# 8x8matrix_tlc4.net
KiCad netlist of a schematic drawn in EAGLE
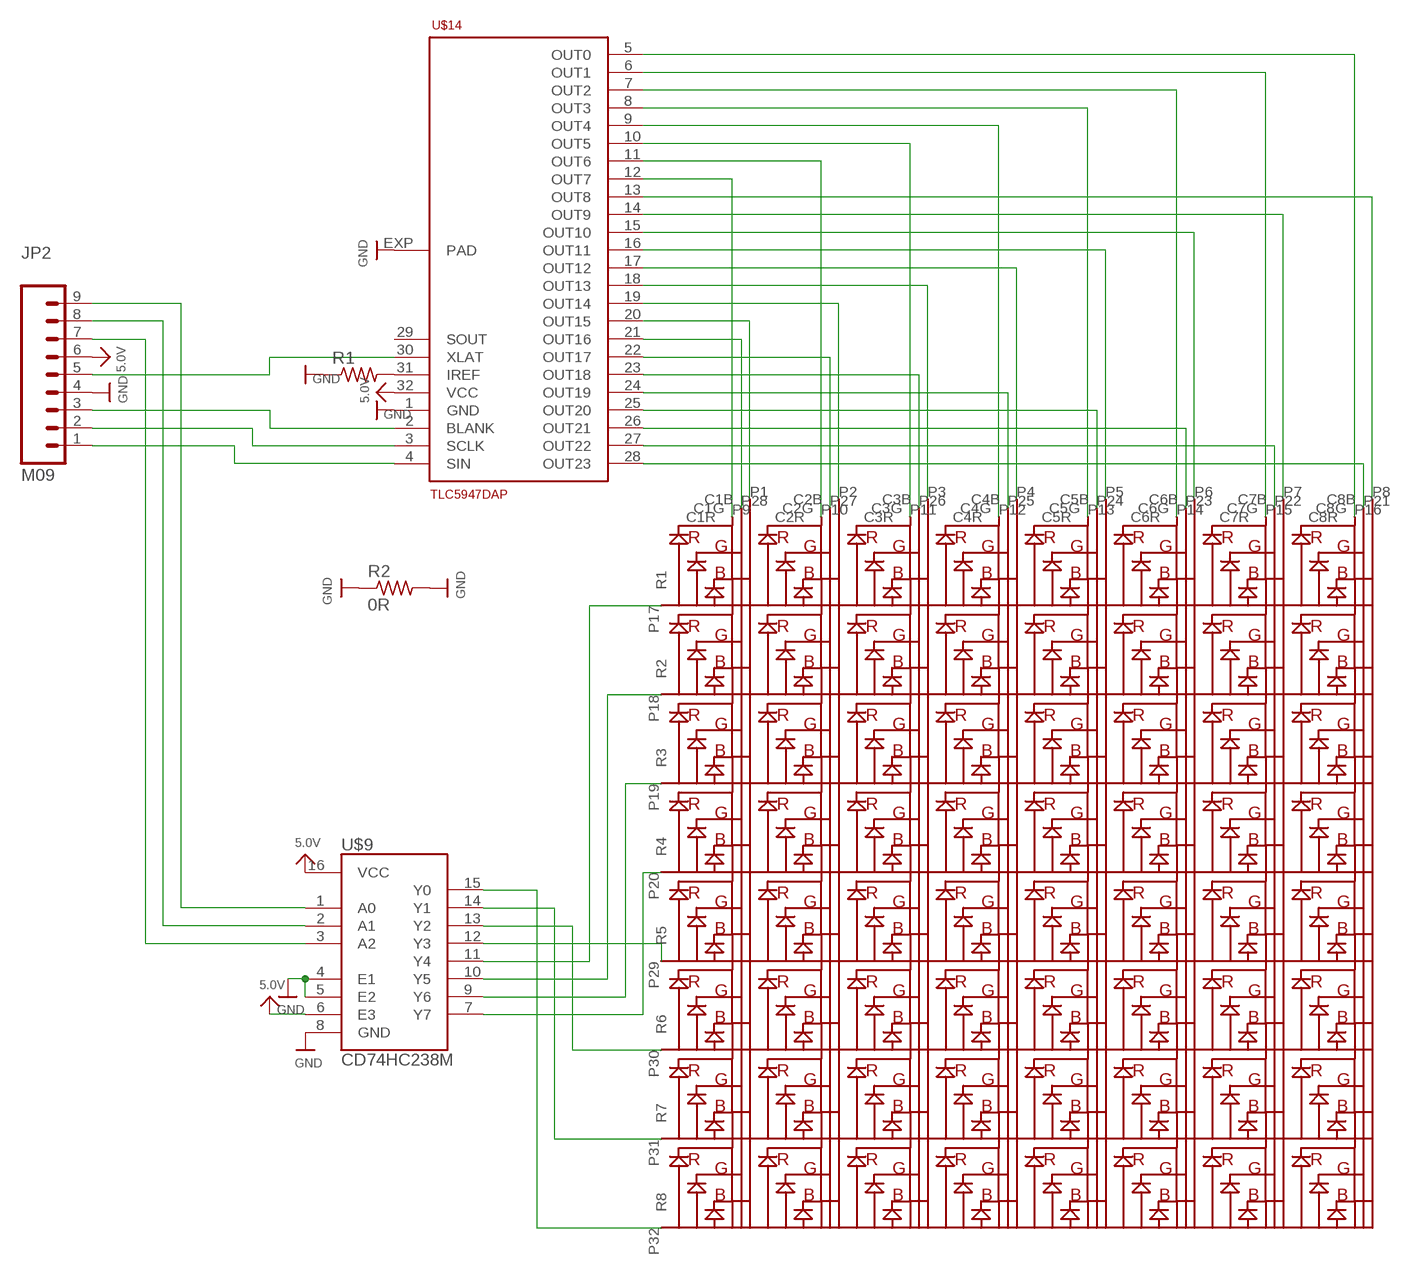
[diagram p0: schematic, sheet 1]

(export (version "E")
  (design (tool "Eeschema 10.0.6"))
  (components
    (comp (ref "JP2")
      (value "M09")
      (footprint "eagle-import:1X09")
      (libsource (lib "eagle-import") (part "M09"))
    )
    (comp (ref "R1")
      (value "R-US_R0805")
      (footprint "eagle-import:R0805")
      (libsource (lib "eagle-import") (part "R-US_R0805"))
    )
    (comp (ref "R2")
      (value "0R")
      (footprint "eagle-import:M1206")
      (libsource (lib "eagle-import") (part "R-US_M1206"))
    )
    (comp (ref "U$1")
      (value "GTM2088ARGB")
      (footprint "eagle-import:8X8MATRIX")
      (libsource (lib "eagle-import") (part "GTM2088ARGB"))
    )
    (comp (ref "U$9")
      (value "CD74HC238M")
      (footprint "eagle-import:SO-16")
      (libsource (lib "eagle-import") (part "CD74HC238M"))
    )
    (comp (ref "U$14")
      (value "TLC5947DAP")
      (footprint "eagle-import:HTSSOP32DAP")
      (libsource (lib "eagle-import") (part "TLC5947DAP"))
    )
  )
  (nets
    (net (code "1") (name "5.0V") (class "Default")
      (node (ref "JP2") (pin "6") (pinfunction "6_6") (pintype "passive"))
      (node (ref "U$14") (pin "32") (pinfunction "VCC_32") (pintype "bidirectional"))
      (node (ref "U$9") (pin "16") (pinfunction "VCC_16") (pintype "bidirectional"))
      (node (ref "U$9") (pin "6") (pinfunction "E3_6") (pintype "bidirectional"))
    )
    (net (code "2") (name "GND") (class "Default")
      (node (ref "JP2") (pin "4") (pinfunction "4_4") (pintype "passive"))
      (node (ref "R1") (pin "1") (pinfunction "1_1") (pintype "passive"))
      (node (ref "R2") (pin "1") (pinfunction "1_1") (pintype "passive"))
      (node (ref "R2") (pin "2") (pinfunction "2_2") (pintype "passive"))
      (node (ref "U$14") (pin "1") (pinfunction "GND_1") (pintype "bidirectional"))
      (node (ref "U$14") (pin "EXP") (pinfunction "PAD_EXP") (pintype "bidirectional"))
      (node (ref "U$9") (pin "4") (pinfunction "E1_4") (pintype "bidirectional"))
      (node (ref "U$9") (pin "5") (pinfunction "E2_5") (pintype "bidirectional"))
      (node (ref "U$9") (pin "8") (pinfunction "GND_8") (pintype "bidirectional"))
    )
    (net (code "3") (name "Net-(U$1-C1B)") (class "Default")
      (node (ref "U$1") (pin "P1") (pinfunction "C1B_P1") (pintype "bidirectional"))
      (node (ref "U$14") (pin "20") (pinfunction "OUT15_20") (pintype "bidirectional"))
    )
    (net (code "4") (name "Net-(U$1-C1G)") (class "Default")
      (node (ref "U$1") (pin "P28") (pinfunction "C1G_P28") (pintype "bidirectional"))
      (node (ref "U$14") (pin "21") (pinfunction "OUT16_21") (pintype "bidirectional"))
    )
    (net (code "5") (name "Net-(U$1-C1R)") (class "Default")
      (node (ref "U$1") (pin "P9") (pinfunction "C1R_P9") (pintype "bidirectional"))
      (node (ref "U$14") (pin "12") (pinfunction "OUT7_12") (pintype "bidirectional"))
    )
    (net (code "6") (name "Net-(U$1-C2B)") (class "Default")
      (node (ref "U$1") (pin "P2") (pinfunction "C2B_P2") (pintype "bidirectional"))
      (node (ref "U$14") (pin "19") (pinfunction "OUT14_19") (pintype "bidirectional"))
    )
    (net (code "7") (name "Net-(U$1-C2G)") (class "Default")
      (node (ref "U$1") (pin "P27") (pinfunction "C2G_P27") (pintype "bidirectional"))
      (node (ref "U$14") (pin "22") (pinfunction "OUT17_22") (pintype "bidirectional"))
    )
    (net (code "8") (name "Net-(U$1-C2R)") (class "Default")
      (node (ref "U$1") (pin "P10") (pinfunction "C2R_P10") (pintype "bidirectional"))
      (node (ref "U$14") (pin "11") (pinfunction "OUT6_11") (pintype "bidirectional"))
    )
    (net (code "9") (name "Net-(U$1-C3B)") (class "Default")
      (node (ref "U$1") (pin "P3") (pinfunction "C3B_P3") (pintype "bidirectional"))
      (node (ref "U$14") (pin "18") (pinfunction "OUT13_18") (pintype "bidirectional"))
    )
    (net (code "10") (name "Net-(U$1-C3G)") (class "Default")
      (node (ref "U$1") (pin "P26") (pinfunction "C3G_P26") (pintype "bidirectional"))
      (node (ref "U$14") (pin "23") (pinfunction "OUT18_23") (pintype "bidirectional"))
    )
    (net (code "11") (name "Net-(U$1-C3R)") (class "Default")
      (node (ref "U$1") (pin "P11") (pinfunction "C3R_P11") (pintype "bidirectional"))
      (node (ref "U$14") (pin "10") (pinfunction "OUT5_10") (pintype "bidirectional"))
    )
    (net (code "12") (name "Net-(U$1-C4B)") (class "Default")
      (node (ref "U$1") (pin "P4") (pinfunction "C4B_P4") (pintype "bidirectional"))
      (node (ref "U$14") (pin "17") (pinfunction "OUT12_17") (pintype "bidirectional"))
    )
    (net (code "13") (name "Net-(U$1-C4G)") (class "Default")
      (node (ref "U$1") (pin "P25") (pinfunction "C4G_P25") (pintype "bidirectional"))
      (node (ref "U$14") (pin "24") (pinfunction "OUT19_24") (pintype "bidirectional"))
    )
    (net (code "14") (name "Net-(U$1-C4R)") (class "Default")
      (node (ref "U$1") (pin "P12") (pinfunction "C4R_P12") (pintype "bidirectional"))
      (node (ref "U$14") (pin "9") (pinfunction "OUT4_9") (pintype "bidirectional"))
    )
    (net (code "15") (name "Net-(U$1-C5B)") (class "Default")
      (node (ref "U$1") (pin "P5") (pinfunction "C5B_P5") (pintype "bidirectional"))
      (node (ref "U$14") (pin "16") (pinfunction "OUT11_16") (pintype "bidirectional"))
    )
    (net (code "16") (name "Net-(U$1-C5G)") (class "Default")
      (node (ref "U$1") (pin "P24") (pinfunction "C5G_P24") (pintype "bidirectional"))
      (node (ref "U$14") (pin "25") (pinfunction "OUT20_25") (pintype "bidirectional"))
    )
    (net (code "17") (name "Net-(U$1-C5R)") (class "Default")
      (node (ref "U$1") (pin "P13") (pinfunction "C5R_P13") (pintype "bidirectional"))
      (node (ref "U$14") (pin "8") (pinfunction "OUT3_8") (pintype "bidirectional"))
    )
    (net (code "18") (name "Net-(U$1-C6B)") (class "Default")
      (node (ref "U$1") (pin "P6") (pinfunction "C6B_P6") (pintype "bidirectional"))
      (node (ref "U$14") (pin "15") (pinfunction "OUT10_15") (pintype "bidirectional"))
    )
    (net (code "19") (name "Net-(U$1-C6G)") (class "Default")
      (node (ref "U$1") (pin "P23") (pinfunction "C6G_P23") (pintype "bidirectional"))
      (node (ref "U$14") (pin "26") (pinfunction "OUT21_26") (pintype "bidirectional"))
    )
    (net (code "20") (name "Net-(U$1-C6R)") (class "Default")
      (node (ref "U$1") (pin "P14") (pinfunction "C6R_P14") (pintype "bidirectional"))
      (node (ref "U$14") (pin "7") (pinfunction "OUT2_7") (pintype "bidirectional"))
    )
    (net (code "21") (name "Net-(U$1-C7B)") (class "Default")
      (node (ref "U$1") (pin "P7") (pinfunction "C7B_P7") (pintype "bidirectional"))
      (node (ref "U$14") (pin "14") (pinfunction "OUT9_14") (pintype "bidirectional"))
    )
    (net (code "22") (name "Net-(U$1-C7G)") (class "Default")
      (node (ref "U$1") (pin "P22") (pinfunction "C7G_P22") (pintype "bidirectional"))
      (node (ref "U$14") (pin "27") (pinfunction "OUT22_27") (pintype "bidirectional"))
    )
    (net (code "23") (name "Net-(U$1-C7R)") (class "Default")
      (node (ref "U$1") (pin "P15") (pinfunction "C7R_P15") (pintype "bidirectional"))
      (node (ref "U$14") (pin "6") (pinfunction "OUT1_6") (pintype "bidirectional"))
    )
    (net (code "24") (name "Net-(U$1-C8B)") (class "Default")
      (node (ref "U$1") (pin "P8") (pinfunction "C8B_P8") (pintype "bidirectional"))
      (node (ref "U$14") (pin "13") (pinfunction "OUT8_13") (pintype "bidirectional"))
    )
    (net (code "25") (name "Net-(U$1-C8G)") (class "Default")
      (node (ref "U$1") (pin "P21") (pinfunction "C8G_P21") (pintype "bidirectional"))
      (node (ref "U$14") (pin "28") (pinfunction "OUT23_28") (pintype "bidirectional"))
    )
    (net (code "26") (name "Net-(U$1-C8R)") (class "Default")
      (node (ref "U$1") (pin "P16") (pinfunction "C8R_P16") (pintype "bidirectional"))
      (node (ref "U$14") (pin "5") (pinfunction "OUT0_5") (pintype "bidirectional"))
    )
    (net (code "27") (name "Net-(U$1-R1)") (class "Default")
      (node (ref "U$1") (pin "P17") (pinfunction "R1_P17") (pintype "bidirectional"))
      (node (ref "U$9") (pin "11") (pinfunction "Y4_11") (pintype "bidirectional"))
    )
    (net (code "28") (name "Net-(U$1-R2)") (class "Default")
      (node (ref "U$1") (pin "P18") (pinfunction "R2_P18") (pintype "bidirectional"))
      (node (ref "U$9") (pin "10") (pinfunction "Y5_10") (pintype "bidirectional"))
    )
    (net (code "29") (name "Net-(U$1-R3)") (class "Default")
      (node (ref "U$1") (pin "P19") (pinfunction "R3_P19") (pintype "bidirectional"))
      (node (ref "U$9") (pin "9") (pinfunction "Y6_9") (pintype "bidirectional"))
    )
    (net (code "30") (name "Net-(U$1-R4)") (class "Default")
      (node (ref "U$1") (pin "P20") (pinfunction "R4_P20") (pintype "bidirectional"))
      (node (ref "U$9") (pin "7") (pinfunction "Y7_7") (pintype "bidirectional"))
    )
    (net (code "31") (name "Net-(U$1-R5)") (class "Default")
      (node (ref "U$1") (pin "P29") (pinfunction "R5_P29") (pintype "bidirectional"))
      (node (ref "U$9") (pin "12") (pinfunction "Y3_12") (pintype "bidirectional"))
    )
    (net (code "32") (name "Net-(U$1-R6)") (class "Default")
      (node (ref "U$1") (pin "P30") (pinfunction "R6_P30") (pintype "bidirectional"))
      (node (ref "U$9") (pin "13") (pinfunction "Y2_13") (pintype "bidirectional"))
    )
    (net (code "33") (name "Net-(U$1-R7)") (class "Default")
      (node (ref "U$1") (pin "P31") (pinfunction "R7_P31") (pintype "bidirectional"))
      (node (ref "U$9") (pin "14") (pinfunction "Y1_14") (pintype "bidirectional"))
    )
    (net (code "34") (name "Net-(U$1-R8)") (class "Default")
      (node (ref "U$1") (pin "P32") (pinfunction "R8_P32") (pintype "bidirectional"))
      (node (ref "U$9") (pin "15") (pinfunction "Y0_15") (pintype "bidirectional"))
    )
    (net (code "35") (name "Net-(U$9-A0)") (class "Default")
      (node (ref "JP2") (pin "9") (pinfunction "9_9") (pintype "passive"))
      (node (ref "U$9") (pin "1") (pinfunction "A0_1") (pintype "bidirectional"))
    )
    (net (code "36") (name "Net-(U$9-A1)") (class "Default")
      (node (ref "JP2") (pin "8") (pinfunction "8_8") (pintype "passive"))
      (node (ref "U$9") (pin "2") (pinfunction "A1_2") (pintype "bidirectional"))
    )
    (net (code "37") (name "Net-(U$9-A2)") (class "Default")
      (node (ref "JP2") (pin "7") (pinfunction "7_7") (pintype "passive"))
      (node (ref "U$9") (pin "3") (pinfunction "A2_3") (pintype "bidirectional"))
    )
    (net (code "38") (name "Net-(U$14-BLANK)") (class "Default")
      (node (ref "JP2") (pin "3") (pinfunction "3_3") (pintype "passive"))
      (node (ref "U$14") (pin "2") (pinfunction "BLANK_2") (pintype "bidirectional"))
    )
    (net (code "39") (name "Net-(U$14-IREF)") (class "Default")
      (node (ref "R1") (pin "2") (pinfunction "2_2") (pintype "passive"))
      (node (ref "U$14") (pin "31") (pinfunction "IREF_31") (pintype "bidirectional"))
    )
    (net (code "40") (name "Net-(U$14-SCLK)") (class "Default")
      (node (ref "JP2") (pin "2") (pinfunction "2_2") (pintype "passive"))
      (node (ref "U$14") (pin "3") (pinfunction "SCLK_3") (pintype "bidirectional"))
    )
    (net (code "41") (name "Net-(U$14-SIN)") (class "Default")
      (node (ref "JP2") (pin "1") (pinfunction "1_1") (pintype "passive"))
      (node (ref "U$14") (pin "4") (pinfunction "SIN_4") (pintype "bidirectional"))
    )
    (net (code "42") (name "Net-(U$14-XLAT)") (class "Default")
      (node (ref "JP2") (pin "5") (pinfunction "5_5") (pintype "passive"))
      (node (ref "U$14") (pin "30") (pinfunction "XLAT_30") (pintype "bidirectional"))
    )
    (net (code "43") (name "unconnected-(U$14-SOUT-Pad29)") (class "Default")
      (node (ref "U$14") (pin "29") (pinfunction "SOUT_29") (pintype "bidirectional"))
    )
  )
)
